# amp_test_filter_route_3.net
KiCad netlist of a schematic drawn in EAGLE
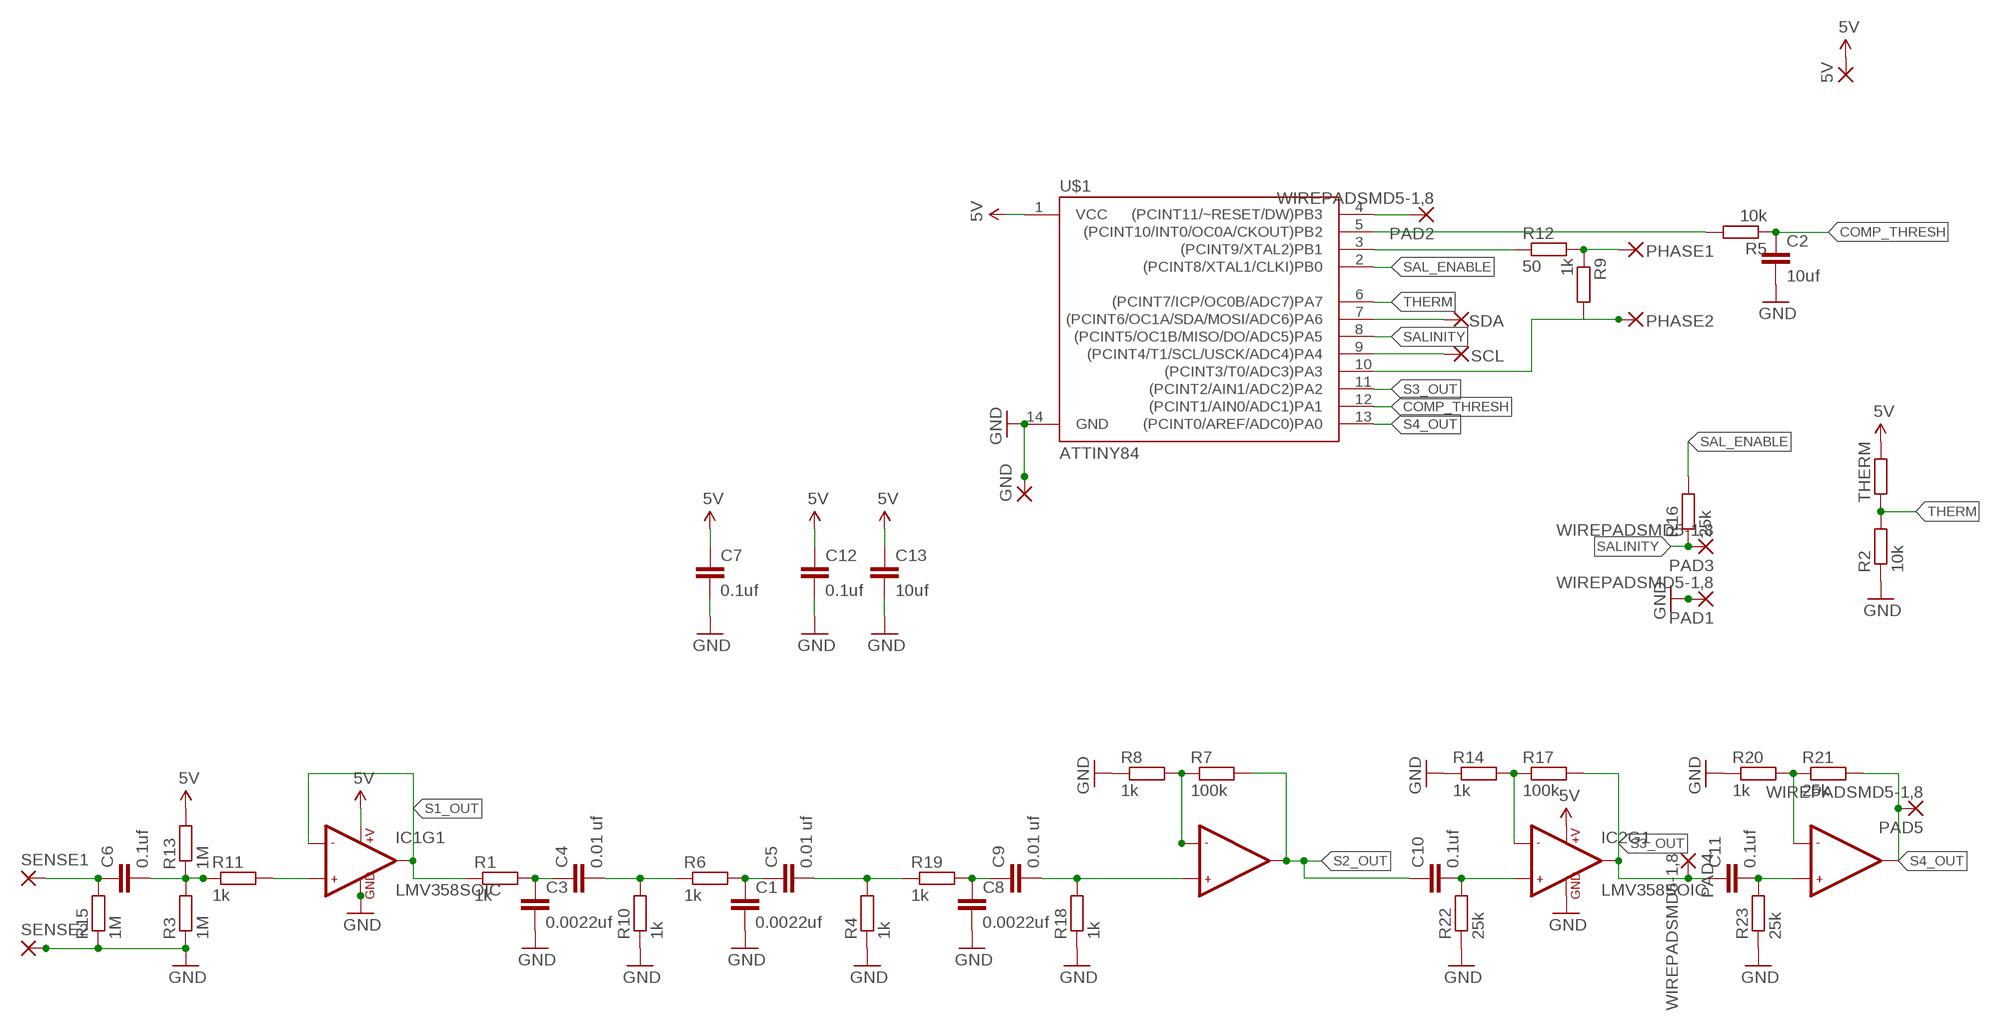
[diagram p0: schematic, sheet 1]

(export (version "E")
  (design (tool "Eeschema 10.0.6"))
  (components
    (comp (ref "5V")
      (value "SMD5")
      (footprint "eagle-import:SMD2,54-5,08")
      (libsource (lib "eagle-import") (part "SMD5"))
    )
    (comp (ref "C1")
      (value "0.0022uf")
      (footprint "eagle-import:C0603")
      (libsource (lib "eagle-import") (part "C-EUC0603"))
    )
    (comp (ref "C2")
      (value "10uf")
      (footprint "eagle-import:C0603")
      (libsource (lib "eagle-import") (part "C-EUC0603"))
    )
    (comp (ref "C3")
      (value "0.0022uf")
      (footprint "eagle-import:C0603")
      (libsource (lib "eagle-import") (part "C-EUC0603"))
    )
    (comp (ref "C4")
      (value "0.01 uf")
      (footprint "eagle-import:C0603")
      (libsource (lib "eagle-import") (part "C-EUC0603"))
    )
    (comp (ref "C5")
      (value "0.01 uf")
      (footprint "eagle-import:C0603")
      (libsource (lib "eagle-import") (part "C-EUC0603"))
    )
    (comp (ref "C6")
      (value "0.1uf")
      (footprint "eagle-import:C0603")
      (libsource (lib "eagle-import") (part "C-EUC0603"))
    )
    (comp (ref "C7")
      (value "0.1uf")
      (footprint "eagle-import:C0603")
      (libsource (lib "eagle-import") (part "C-EUC0603"))
    )
    (comp (ref "C8")
      (value "0.0022uf")
      (footprint "eagle-import:C0603")
      (libsource (lib "eagle-import") (part "C-EUC0603"))
    )
    (comp (ref "C9")
      (value "0.01 uf")
      (footprint "eagle-import:C0603")
      (libsource (lib "eagle-import") (part "C-EUC0603"))
    )
    (comp (ref "C10")
      (value "0.1uf")
      (footprint "eagle-import:C0603")
      (libsource (lib "eagle-import") (part "C-EUC0603"))
    )
    (comp (ref "C11")
      (value "0.1uf")
      (footprint "eagle-import:C0603")
      (libsource (lib "eagle-import") (part "C-EUC0603"))
    )
    (comp (ref "C12")
      (value "0.1uf")
      (footprint "eagle-import:C0603")
      (libsource (lib "eagle-import") (part "C-EUC0603"))
    )
    (comp (ref "C13")
      (value "10uf")
      (footprint "eagle-import:C0603")
      (libsource (lib "eagle-import") (part "C-EUC0603"))
    )
    (comp (ref "GND")
      (value "SMD5")
      (footprint "eagle-import:SMD2,54-5,08")
      (libsource (lib "eagle-import") (part "SMD5"))
    )
    (comp (ref "IC1")
      (value "LMV358SOIC")
      (footprint "eagle-import:SO08")
      (libsource (lib "eagle-import") (part "LMV358SOIC"))
    )
    (comp (ref "IC2")
      (value "LMV358SOIC")
      (footprint "eagle-import:SO08")
      (libsource (lib "eagle-import") (part "LMV358SOIC"))
    )
    (comp (ref "PAD1")
      (value "WIREPADSMD5-1,8")
      (footprint "eagle-import:5-1,8")
      (libsource (lib "eagle-import") (part "WIREPADSMD5-1,8"))
    )
    (comp (ref "PAD2")
      (value "WIREPADSMD5-1,8")
      (footprint "eagle-import:5-1,8")
      (libsource (lib "eagle-import") (part "WIREPADSMD5-1,8"))
    )
    (comp (ref "PAD3")
      (value "WIREPADSMD5-1,8")
      (footprint "eagle-import:5-1,8")
      (libsource (lib "eagle-import") (part "WIREPADSMD5-1,8"))
    )
    (comp (ref "PAD4")
      (value "WIREPADSMD5-1,8")
      (footprint "eagle-import:5-1,8")
      (libsource (lib "eagle-import") (part "WIREPADSMD5-1,8"))
    )
    (comp (ref "PAD5")
      (value "WIREPADSMD5-1,8")
      (footprint "eagle-import:5-1,8")
      (libsource (lib "eagle-import") (part "WIREPADSMD5-1,8"))
    )
    (comp (ref "PHASE1")
      (value "SMD5")
      (footprint "eagle-import:SMD2,54-5,08")
      (libsource (lib "eagle-import") (part "SMD5"))
    )
    (comp (ref "PHASE2")
      (value "SMD5")
      (footprint "eagle-import:SMD2,54-5,08")
      (libsource (lib "eagle-import") (part "SMD5"))
    )
    (comp (ref "R1")
      (value "1k")
      (footprint "eagle-import:R0603")
      (libsource (lib "eagle-import") (part "R-EU_R0603"))
    )
    (comp (ref "R2")
      (value "10k")
      (footprint "eagle-import:R0603")
      (libsource (lib "eagle-import") (part "R-EU_R0603"))
    )
    (comp (ref "R3")
      (value "1M")
      (footprint "eagle-import:R0603")
      (libsource (lib "eagle-import") (part "R-EU_R0603"))
    )
    (comp (ref "R4")
      (value "1k")
      (footprint "eagle-import:R0603")
      (libsource (lib "eagle-import") (part "R-EU_R0603"))
    )
    (comp (ref "R5")
      (value "10k")
      (footprint "eagle-import:R0603")
      (libsource (lib "eagle-import") (part "R-EU_R0603"))
    )
    (comp (ref "R6")
      (value "1k")
      (footprint "eagle-import:R0603")
      (libsource (lib "eagle-import") (part "R-EU_R0603"))
    )
    (comp (ref "R7")
      (value "100k")
      (footprint "eagle-import:R0603")
      (libsource (lib "eagle-import") (part "R-EU_R0603"))
    )
    (comp (ref "R8")
      (value "1k")
      (footprint "eagle-import:R0603")
      (libsource (lib "eagle-import") (part "R-EU_R0603"))
    )
    (comp (ref "R9")
      (value "1k")
      (footprint "eagle-import:R0603")
      (libsource (lib "eagle-import") (part "R-EU_R0603"))
    )
    (comp (ref "R10")
      (value "1k")
      (footprint "eagle-import:R0603")
      (libsource (lib "eagle-import") (part "R-EU_R0603"))
    )
    (comp (ref "R11")
      (value "1k")
      (footprint "eagle-import:R0603")
      (libsource (lib "eagle-import") (part "R-EU_R0603"))
    )
    (comp (ref "R12")
      (value "50")
      (footprint "eagle-import:R0603")
      (libsource (lib "eagle-import") (part "R-EU_R0603"))
    )
    (comp (ref "R13")
      (value "1M")
      (footprint "eagle-import:R0603")
      (libsource (lib "eagle-import") (part "R-EU_R0603"))
    )
    (comp (ref "R14")
      (value "1k")
      (footprint "eagle-import:R0603")
      (libsource (lib "eagle-import") (part "R-EU_R0603"))
    )
    (comp (ref "R15")
      (value "1M")
      (footprint "eagle-import:R0603")
      (libsource (lib "eagle-import") (part "R-EU_R0603"))
    )
    (comp (ref "R16")
      (value "25k")
      (footprint "eagle-import:R0603")
      (libsource (lib "eagle-import") (part "R-EU_R0603"))
    )
    (comp (ref "R17")
      (value "100k")
      (footprint "eagle-import:R0603")
      (libsource (lib "eagle-import") (part "R-EU_R0603"))
    )
    (comp (ref "R18")
      (value "1k")
      (footprint "eagle-import:R0603")
      (libsource (lib "eagle-import") (part "R-EU_R0603"))
    )
    (comp (ref "R19")
      (value "1k")
      (footprint "eagle-import:R0603")
      (libsource (lib "eagle-import") (part "R-EU_R0603"))
    )
    (comp (ref "R20")
      (value "1k")
      (footprint "eagle-import:R0603")
      (libsource (lib "eagle-import") (part "R-EU_R0603"))
    )
    (comp (ref "R21")
      (value "25k")
      (footprint "eagle-import:R0603")
      (libsource (lib "eagle-import") (part "R-EU_R0603"))
    )
    (comp (ref "R22")
      (value "25k")
      (footprint "eagle-import:R0603")
      (libsource (lib "eagle-import") (part "R-EU_R0603"))
    )
    (comp (ref "R23")
      (value "25k")
      (footprint "eagle-import:R0603")
      (libsource (lib "eagle-import") (part "R-EU_R0603"))
    )
    (comp (ref "SCL")
      (value "SMD5")
      (footprint "eagle-import:SMD2,54-5,08")
      (libsource (lib "eagle-import") (part "SMD5"))
    )
    (comp (ref "SDA")
      (value "SMD5")
      (footprint "eagle-import:SMD2,54-5,08")
      (libsource (lib "eagle-import") (part "SMD5"))
    )
    (comp (ref "SENSE1")
      (value "SMD5")
      (footprint "eagle-import:SMD2,54-5,08")
      (libsource (lib "eagle-import") (part "SMD5"))
    )
    (comp (ref "SENSE2")
      (value "SMD5")
      (footprint "eagle-import:SMD2,54-5,08")
      (libsource (lib "eagle-import") (part "SMD5"))
    )
    (comp (ref "THERM")
      (value "R-EU_R0603")
      (footprint "eagle-import:R0603")
      (libsource (lib "eagle-import") (part "R-EU_R0603"))
    )
    (comp (ref "U$1")
      (value "ATTINY84")
      (footprint "eagle-import:SO14")
      (libsource (lib "eagle-import") (part "ATTINY84"))
    )
  )
  (nets
    (net (code "1") (name "5V") (class "Default")
      (node (ref "5V") (pin "1") (pinfunction "P_1") (pintype "passive"))
      (node (ref "C12") (pin "1") (pinfunction "1_1") (pintype "passive"))
      (node (ref "C13") (pin "1") (pinfunction "1_1") (pintype "passive"))
      (node (ref "C7") (pin "1") (pinfunction "1_1") (pintype "passive"))
      (node (ref "IC1") (pin "8") (pinfunction "+V_8") (pintype "power_in"))
      (node (ref "IC2") (pin "8") (pinfunction "+V_8") (pintype "power_in"))
      (node (ref "R13") (pin "2") (pinfunction "2_2") (pintype "passive"))
      (node (ref "THERM") (pin "2") (pinfunction "2_2") (pintype "passive"))
      (node (ref "U$1") (pin "1") (pinfunction "VCC_1") (pintype "bidirectional"))
    )
    (net (code "2") (name "COMP_THRESH") (class "Default")
      (node (ref "C2") (pin "1") (pinfunction "1_1") (pintype "passive"))
      (node (ref "R5") (pin "1") (pinfunction "1_1") (pintype "passive"))
      (node (ref "U$1") (pin "12") (pinfunction "(PCINT1/AIN0/ADC1)PA1_12") (pintype "bidirectional"))
    )
    (net (code "3") (name "GND") (class "Default")
      (node (ref "C1") (pin "2") (pinfunction "2_2") (pintype "passive"))
      (node (ref "C12") (pin "2") (pinfunction "2_2") (pintype "passive"))
      (node (ref "C13") (pin "2") (pinfunction "2_2") (pintype "passive"))
      (node (ref "C2") (pin "2") (pinfunction "2_2") (pintype "passive"))
      (node (ref "C3") (pin "2") (pinfunction "2_2") (pintype "passive"))
      (node (ref "C7") (pin "2") (pinfunction "2_2") (pintype "passive"))
      (node (ref "C8") (pin "2") (pinfunction "2_2") (pintype "passive"))
      (node (ref "GND") (pin "1") (pinfunction "P_1") (pintype "passive"))
      (node (ref "IC1") (pin "4") (pinfunction "GND_4") (pintype "power_in"))
      (node (ref "IC2") (pin "4") (pinfunction "GND_4") (pintype "power_in"))
      (node (ref "PAD1") (pin "1") (pinfunction "P_1") (pintype "passive"))
      (node (ref "R10") (pin "1") (pinfunction "1_1") (pintype "passive"))
      (node (ref "R14") (pin "1") (pinfunction "1_1") (pintype "passive"))
      (node (ref "R15") (pin "1") (pinfunction "1_1") (pintype "passive"))
      (node (ref "R18") (pin "1") (pinfunction "1_1") (pintype "passive"))
      (node (ref "R2") (pin "1") (pinfunction "1_1") (pintype "passive"))
      (node (ref "R20") (pin "1") (pinfunction "1_1") (pintype "passive"))
      (node (ref "R22") (pin "1") (pinfunction "1_1") (pintype "passive"))
      (node (ref "R23") (pin "1") (pinfunction "1_1") (pintype "passive"))
      (node (ref "R3") (pin "1") (pinfunction "1_1") (pintype "passive"))
      (node (ref "R4") (pin "1") (pinfunction "1_1") (pintype "passive"))
      (node (ref "R8") (pin "1") (pinfunction "1_1") (pintype "passive"))
      (node (ref "SENSE2") (pin "1") (pinfunction "P_1") (pintype "passive"))
      (node (ref "U$1") (pin "14") (pinfunction "GND_14") (pintype "bidirectional"))
    )
    (net (code "4") (name "Net-(C1-Pad1)") (class "Default")
      (node (ref "C1") (pin "1") (pinfunction "1_1") (pintype "passive"))
      (node (ref "C5") (pin "1") (pinfunction "1_1") (pintype "passive"))
      (node (ref "R6") (pin "2") (pinfunction "2_2") (pintype "passive"))
    )
    (net (code "5") (name "Net-(C3-Pad1)") (class "Default")
      (node (ref "C3") (pin "1") (pinfunction "1_1") (pintype "passive"))
      (node (ref "C4") (pin "1") (pinfunction "1_1") (pintype "passive"))
      (node (ref "R1") (pin "2") (pinfunction "2_2") (pintype "passive"))
    )
    (net (code "6") (name "Net-(C4-Pad2)") (class "Default")
      (node (ref "C4") (pin "2") (pinfunction "2_2") (pintype "passive"))
      (node (ref "R10") (pin "2") (pinfunction "2_2") (pintype "passive"))
      (node (ref "R6") (pin "1") (pinfunction "1_1") (pintype "passive"))
    )
    (net (code "7") (name "Net-(C5-Pad2)") (class "Default")
      (node (ref "C5") (pin "2") (pinfunction "2_2") (pintype "passive"))
      (node (ref "R19") (pin "1") (pinfunction "1_1") (pintype "passive"))
      (node (ref "R4") (pin "2") (pinfunction "2_2") (pintype "passive"))
    )
    (net (code "8") (name "Net-(C6-Pad2)") (class "Default")
      (node (ref "C6") (pin "2") (pinfunction "2_2") (pintype "passive"))
      (node (ref "R11") (pin "1") (pinfunction "1_1") (pintype "passive"))
      (node (ref "R13") (pin "1") (pinfunction "1_1") (pintype "passive"))
      (node (ref "R3") (pin "2") (pinfunction "2_2") (pintype "passive"))
    )
    (net (code "9") (name "Net-(C8-Pad1)") (class "Default")
      (node (ref "C8") (pin "1") (pinfunction "1_1") (pintype "passive"))
      (node (ref "C9") (pin "1") (pinfunction "1_1") (pintype "passive"))
      (node (ref "R19") (pin "2") (pinfunction "2_2") (pintype "passive"))
    )
    (net (code "10") (name "Net-(IC1A-+IN1)") (class "Default")
      (node (ref "IC1") (pin "3") (pinfunction "+IN1_3") (pintype "input"))
      (node (ref "R11") (pin "2") (pinfunction "2_2") (pintype "passive"))
    )
    (net (code "11") (name "Net-(IC1B-+IN2)") (class "Default")
      (node (ref "C9") (pin "2") (pinfunction "2_2") (pintype "passive"))
      (node (ref "IC1") (pin "5") (pinfunction "+IN2_5") (pintype "input"))
      (node (ref "R18") (pin "2") (pinfunction "2_2") (pintype "passive"))
    )
    (net (code "12") (name "Net-(IC1B--IN2)") (class "Default")
      (node (ref "IC1") (pin "6") (pinfunction "-IN2_6") (pintype "input"))
      (node (ref "R7") (pin "1") (pinfunction "1_1") (pintype "passive"))
      (node (ref "R8") (pin "2") (pinfunction "2_2") (pintype "passive"))
    )
    (net (code "13") (name "Net-(IC2A-+IN1)") (class "Default")
      (node (ref "C10") (pin "2") (pinfunction "2_2") (pintype "passive"))
      (node (ref "IC2") (pin "3") (pinfunction "+IN1_3") (pintype "input"))
      (node (ref "R22") (pin "2") (pinfunction "2_2") (pintype "passive"))
    )
    (net (code "14") (name "Net-(IC2A--IN1)") (class "Default")
      (node (ref "IC2") (pin "2") (pinfunction "-IN1_2") (pintype "input"))
      (node (ref "R14") (pin "2") (pinfunction "2_2") (pintype "passive"))
      (node (ref "R17") (pin "1") (pinfunction "1_1") (pintype "passive"))
    )
    (net (code "15") (name "Net-(IC2B-+IN2)") (class "Default")
      (node (ref "C11") (pin "2") (pinfunction "2_2") (pintype "passive"))
      (node (ref "IC2") (pin "5") (pinfunction "+IN2_5") (pintype "input"))
      (node (ref "R23") (pin "2") (pinfunction "2_2") (pintype "passive"))
    )
    (net (code "16") (name "Net-(IC2B--IN2)") (class "Default")
      (node (ref "IC2") (pin "6") (pinfunction "-IN2_6") (pintype "input"))
      (node (ref "R20") (pin "2") (pinfunction "2_2") (pintype "passive"))
      (node (ref "R21") (pin "1") (pinfunction "1_1") (pintype "passive"))
    )
    (net (code "17") (name "Net-(PAD2-P)") (class "Default")
      (node (ref "PAD2") (pin "1") (pinfunction "P_1") (pintype "passive"))
      (node (ref "U$1") (pin "4") (pinfunction "(PCINT11/~{RESET/DW})PB3_4") (pintype "bidirectional"))
    )
    (net (code "18") (name "Net-(PHASE1-P)") (class "Default")
      (node (ref "PHASE1") (pin "1") (pinfunction "P_1") (pintype "passive"))
      (node (ref "R12") (pin "2") (pinfunction "2_2") (pintype "passive"))
      (node (ref "R9") (pin "1") (pinfunction "1_1") (pintype "passive"))
    )
    (net (code "19") (name "Net-(PHASE2-P)") (class "Default")
      (node (ref "PHASE2") (pin "1") (pinfunction "P_1") (pintype "passive"))
      (node (ref "R9") (pin "2") (pinfunction "2_2") (pintype "passive"))
      (node (ref "U$1") (pin "10") (pinfunction "(PCINT3/T0/ADC3)PA3_10") (pintype "bidirectional"))
    )
    (net (code "20") (name "Net-(SCL-P)") (class "Default")
      (node (ref "SCL") (pin "1") (pinfunction "P_1") (pintype "passive"))
      (node (ref "U$1") (pin "9") (pinfunction "(PCINT4/T1/SCL/USCK/ADC4)PA4_9") (pintype "bidirectional"))
    )
    (net (code "21") (name "Net-(SDA-P)") (class "Default")
      (node (ref "SDA") (pin "1") (pinfunction "P_1") (pintype "passive"))
      (node (ref "U$1") (pin "7") (pinfunction "(PCINT6/OC1A/SDA/MOSI/ADC6)PA6_7") (pintype "bidirectional"))
    )
    (net (code "22") (name "Net-(SENSE1-P)") (class "Default")
      (node (ref "C6") (pin "1") (pinfunction "1_1") (pintype "passive"))
      (node (ref "R15") (pin "2") (pinfunction "2_2") (pintype "passive"))
      (node (ref "SENSE1") (pin "1") (pinfunction "P_1") (pintype "passive"))
    )
    (net (code "23") (name "Net-(U$1-(PCINT9{slash}XTAL2)PB1)") (class "Default")
      (node (ref "R12") (pin "1") (pinfunction "1_1") (pintype "passive"))
      (node (ref "U$1") (pin "3") (pinfunction "(PCINT9/XTAL2)PB1_3") (pintype "bidirectional"))
    )
    (net (code "24") (name "Net-(U$1-(PCINT10{slash}INT0{slash}OC0A{slash}CKOUT)PB2)") (class "Default")
      (node (ref "R5") (pin "2") (pinfunction "2_2") (pintype "passive"))
      (node (ref "U$1") (pin "5") (pinfunction "(PCINT10/INT0/OC0A/CKOUT)PB2_5") (pintype "bidirectional"))
    )
    (net (code "25") (name "S1_OUT") (class "Default")
      (node (ref "IC1") (pin "1") (pinfunction "OUT1_1") (pintype "output"))
      (node (ref "IC1") (pin "2") (pinfunction "-IN1_2") (pintype "input"))
      (node (ref "R1") (pin "1") (pinfunction "1_1") (pintype "passive"))
    )
    (net (code "26") (name "S2_OUT") (class "Default")
      (node (ref "C10") (pin "1") (pinfunction "1_1") (pintype "passive"))
      (node (ref "IC1") (pin "7") (pinfunction "OUT2_7") (pintype "output"))
      (node (ref "R7") (pin "2") (pinfunction "2_2") (pintype "passive"))
    )
    (net (code "27") (name "S3_OUT") (class "Default")
      (node (ref "C11") (pin "1") (pinfunction "1_1") (pintype "passive"))
      (node (ref "IC2") (pin "1") (pinfunction "OUT1_1") (pintype "output"))
      (node (ref "PAD4") (pin "1") (pinfunction "P_1") (pintype "passive"))
      (node (ref "R17") (pin "2") (pinfunction "2_2") (pintype "passive"))
      (node (ref "U$1") (pin "11") (pinfunction "(PCINT2/AIN1/ADC2)PA2_11") (pintype "bidirectional"))
    )
    (net (code "28") (name "S4_OUT") (class "Default")
      (node (ref "IC2") (pin "7") (pinfunction "OUT2_7") (pintype "output"))
      (node (ref "PAD5") (pin "1") (pinfunction "P_1") (pintype "passive"))
      (node (ref "R21") (pin "2") (pinfunction "2_2") (pintype "passive"))
      (node (ref "U$1") (pin "13") (pinfunction "(PCINT0/AREF/ADC0)PA0_13") (pintype "bidirectional"))
    )
    (net (code "29") (name "SALINITY") (class "Default")
      (node (ref "PAD3") (pin "1") (pinfunction "P_1") (pintype "passive"))
      (node (ref "R16") (pin "1") (pinfunction "1_1") (pintype "passive"))
      (node (ref "U$1") (pin "8") (pinfunction "(PCINT5/OC1B/MISO/DO/ADC5)PA5_8") (pintype "bidirectional"))
    )
    (net (code "30") (name "SAL_ENABLE") (class "Default")
      (node (ref "R16") (pin "2") (pinfunction "2_2") (pintype "passive"))
      (node (ref "U$1") (pin "2") (pinfunction "(PCINT8/XTAL1/CLKI)PB0_2") (pintype "bidirectional"))
    )
    (net (code "31") (name "THERM") (class "Default")
      (node (ref "R2") (pin "2") (pinfunction "2_2") (pintype "passive"))
      (node (ref "THERM") (pin "1") (pinfunction "1_1") (pintype "passive"))
      (node (ref "U$1") (pin "6") (pinfunction "(PCINT7/ICP/OC0B/ADC7)PA7_6") (pintype "bidirectional"))
    )
  )
)
